# Kube_Base_ESP32_HiLetGo.net
KiCad netlist of a schematic drawn in EAGLE
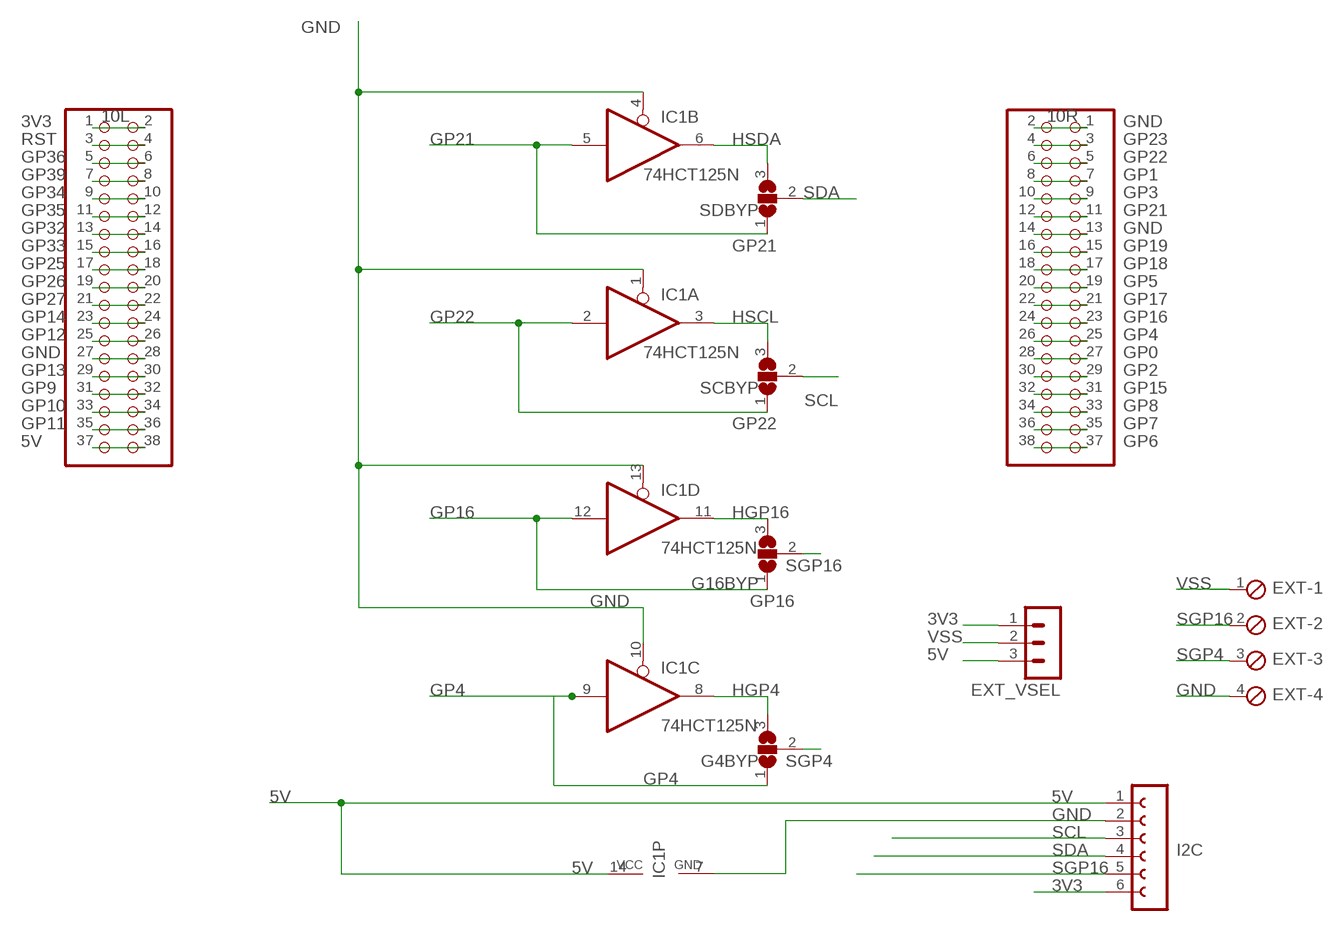
[diagram p0: schematic, sheet 1]

(export (version "E")
  (design (tool "Eeschema 10.0.6"))
  (components
    (comp (ref "10L")
      (value "15")
      (footprint "eagle-import:2X19")
      (libsource (lib "eagle-import") (part "PINHD-2X19"))
    )
    (comp (ref "10R")
      (value "15")
      (footprint "eagle-import:2X19")
      (libsource (lib "eagle-import") (part "PINHD-2X19"))
    )
    (comp (ref "EXT")
      (value "MPT4")
      (footprint "eagle-import:4POL254")
      (libsource (lib "eagle-import") (part "MPT4"))
    )
    (comp (ref "EXT_VSEL")
      (value "MA03-1")
      (footprint "eagle-import:MA03-1")
      (libsource (lib "eagle-import") (part "MA03-1"))
    )
    (comp (ref "G4BYP")
      (value "SJ2W")
      (footprint "eagle-import:SJ_2")
      (libsource (lib "eagle-import") (part "SJ2W"))
    )
    (comp (ref "G16BYP")
      (value "SJ2W")
      (footprint "eagle-import:SJ_2")
      (libsource (lib "eagle-import") (part "SJ2W"))
    )
    (comp (ref "I2C")
      (value "FE06-1")
      (footprint "eagle-import:FE06")
      (libsource (lib "eagle-import") (part "FE06-1"))
    )
    (comp (ref "IC1")
      (value "74HCT125N")
      (footprint "eagle-import:DIL14")
      (libsource (lib "eagle-import") (part "74125NHCT"))
    )
    (comp (ref "SCBYP")
      (value "SJ2W")
      (footprint "eagle-import:SJ_2")
      (libsource (lib "eagle-import") (part "SJ2W"))
    )
    (comp (ref "SDBYP")
      (value "SJ2W")
      (footprint "eagle-import:SJ_2")
      (libsource (lib "eagle-import") (part "SJ2W"))
    )
  )
  (nets
    (net (code "1") (name "/3V3") (class "Default")
      (node (ref "10L") (pin "1") (pinfunction "1_1") (pintype "passive"))
      (node (ref "10L") (pin "2") (pinfunction "2_2") (pintype "passive"))
      (node (ref "EXT_VSEL") (pin "1") (pinfunction "1_1") (pintype "passive"))
      (node (ref "I2C") (pin "6") (pinfunction "6_6") (pintype "passive"))
    )
    (net (code "2") (name "/5V") (class "Default")
      (node (ref "10L") (pin "37") (pinfunction "37_37") (pintype "passive"))
      (node (ref "10L") (pin "38") (pinfunction "38_38") (pintype "passive"))
      (node (ref "EXT_VSEL") (pin "3") (pinfunction "3_3") (pintype "passive"))
      (node (ref "I2C") (pin "1") (pinfunction "1_1") (pintype "passive"))
      (node (ref "IC1") (pin "14") (pinfunction "VCC_14") (pintype "power_in"))
    )
    (net (code "3") (name "/GND") (class "Default")
      (node (ref "10L") (pin "27") (pinfunction "27_27") (pintype "passive"))
      (node (ref "10L") (pin "28") (pinfunction "28_28") (pintype "passive"))
      (node (ref "10R") (pin "1") (pinfunction "1_1") (pintype "passive"))
      (node (ref "10R") (pin "13") (pinfunction "13_13") (pintype "passive"))
      (node (ref "10R") (pin "14") (pinfunction "14_14") (pintype "passive"))
      (node (ref "10R") (pin "2") (pinfunction "2_2") (pintype "passive"))
      (node (ref "EXT") (pin "4") (pinfunction "1_4") (pintype "passive"))
      (node (ref "I2C") (pin "2") (pinfunction "2_2") (pintype "passive"))
      (node (ref "IC1") (pin "1") (pinfunction "OE_1") (pintype "input"))
      (node (ref "IC1") (pin "10") (pinfunction "OE_10") (pintype "input"))
      (node (ref "IC1") (pin "13") (pinfunction "OE_13") (pintype "input"))
      (node (ref "IC1") (pin "4") (pinfunction "OE_4") (pintype "input"))
      (node (ref "IC1") (pin "7") (pinfunction "GND_7") (pintype "power_in"))
    )
    (net (code "4") (name "/GP0") (class "Default")
      (node (ref "10R") (pin "27") (pinfunction "27_27") (pintype "passive"))
      (node (ref "10R") (pin "28") (pinfunction "28_28") (pintype "passive"))
    )
    (net (code "5") (name "/GP1") (class "Default")
      (node (ref "10R") (pin "7") (pinfunction "7_7") (pintype "passive"))
      (node (ref "10R") (pin "8") (pinfunction "8_8") (pintype "passive"))
    )
    (net (code "6") (name "/GP2") (class "Default")
      (node (ref "10R") (pin "29") (pinfunction "29_29") (pintype "passive"))
      (node (ref "10R") (pin "30") (pinfunction "30_30") (pintype "passive"))
    )
    (net (code "7") (name "/GP3") (class "Default")
      (node (ref "10R") (pin "10") (pinfunction "10_10") (pintype "passive"))
      (node (ref "10R") (pin "9") (pinfunction "9_9") (pintype "passive"))
    )
    (net (code "8") (name "/GP4") (class "Default")
      (node (ref "10R") (pin "25") (pinfunction "25_25") (pintype "passive"))
      (node (ref "10R") (pin "26") (pinfunction "26_26") (pintype "passive"))
      (node (ref "G4BYP") (pin "1") (pinfunction "1_1") (pintype "passive"))
      (node (ref "IC1") (pin "9") (pinfunction "I_9") (pintype "input"))
    )
    (net (code "9") (name "/GP5") (class "Default")
      (node (ref "10R") (pin "19") (pinfunction "19_19") (pintype "passive"))
      (node (ref "10R") (pin "20") (pinfunction "20_20") (pintype "passive"))
    )
    (net (code "10") (name "/GP6") (class "Default")
      (node (ref "10R") (pin "37") (pinfunction "37_37") (pintype "passive"))
      (node (ref "10R") (pin "38") (pinfunction "38_38") (pintype "passive"))
    )
    (net (code "11") (name "/GP7") (class "Default")
      (node (ref "10R") (pin "35") (pinfunction "35_35") (pintype "passive"))
      (node (ref "10R") (pin "36") (pinfunction "36_36") (pintype "passive"))
    )
    (net (code "12") (name "/GP8") (class "Default")
      (node (ref "10R") (pin "33") (pinfunction "33_33") (pintype "passive"))
      (node (ref "10R") (pin "34") (pinfunction "34_34") (pintype "passive"))
    )
    (net (code "13") (name "/GP9") (class "Default")
      (node (ref "10L") (pin "31") (pinfunction "31_31") (pintype "passive"))
      (node (ref "10L") (pin "32") (pinfunction "32_32") (pintype "passive"))
    )
    (net (code "14") (name "/GP10") (class "Default")
      (node (ref "10L") (pin "33") (pinfunction "33_33") (pintype "passive"))
      (node (ref "10L") (pin "34") (pinfunction "34_34") (pintype "passive"))
    )
    (net (code "15") (name "/GP11") (class "Default")
      (node (ref "10L") (pin "35") (pinfunction "35_35") (pintype "passive"))
      (node (ref "10L") (pin "36") (pinfunction "36_36") (pintype "passive"))
    )
    (net (code "16") (name "/GP12") (class "Default")
      (node (ref "10L") (pin "25") (pinfunction "25_25") (pintype "passive"))
      (node (ref "10L") (pin "26") (pinfunction "26_26") (pintype "passive"))
    )
    (net (code "17") (name "/GP13") (class "Default")
      (node (ref "10L") (pin "29") (pinfunction "29_29") (pintype "passive"))
      (node (ref "10L") (pin "30") (pinfunction "30_30") (pintype "passive"))
    )
    (net (code "18") (name "/GP14") (class "Default")
      (node (ref "10L") (pin "23") (pinfunction "23_23") (pintype "passive"))
      (node (ref "10L") (pin "24") (pinfunction "24_24") (pintype "passive"))
    )
    (net (code "19") (name "/GP15") (class "Default")
      (node (ref "10R") (pin "31") (pinfunction "31_31") (pintype "passive"))
      (node (ref "10R") (pin "32") (pinfunction "32_32") (pintype "passive"))
    )
    (net (code "20") (name "/GP16") (class "Default")
      (node (ref "10R") (pin "23") (pinfunction "23_23") (pintype "passive"))
      (node (ref "10R") (pin "24") (pinfunction "24_24") (pintype "passive"))
      (node (ref "G16BYP") (pin "1") (pinfunction "1_1") (pintype "passive"))
      (node (ref "IC1") (pin "12") (pinfunction "I_12") (pintype "input"))
    )
    (net (code "21") (name "/GP17") (class "Default")
      (node (ref "10R") (pin "21") (pinfunction "21_21") (pintype "passive"))
      (node (ref "10R") (pin "22") (pinfunction "22_22") (pintype "passive"))
    )
    (net (code "22") (name "/GP18") (class "Default")
      (node (ref "10R") (pin "17") (pinfunction "17_17") (pintype "passive"))
      (node (ref "10R") (pin "18") (pinfunction "18_18") (pintype "passive"))
    )
    (net (code "23") (name "/GP19") (class "Default")
      (node (ref "10R") (pin "15") (pinfunction "15_15") (pintype "passive"))
      (node (ref "10R") (pin "16") (pinfunction "16_16") (pintype "passive"))
    )
    (net (code "24") (name "/GP21") (class "Default")
      (node (ref "10R") (pin "11") (pinfunction "11_11") (pintype "passive"))
      (node (ref "10R") (pin "12") (pinfunction "12_12") (pintype "passive"))
      (node (ref "IC1") (pin "5") (pinfunction "I_5") (pintype "input"))
      (node (ref "SDBYP") (pin "1") (pinfunction "1_1") (pintype "passive"))
    )
    (net (code "25") (name "/GP22") (class "Default")
      (node (ref "10R") (pin "5") (pinfunction "5_5") (pintype "passive"))
      (node (ref "10R") (pin "6") (pinfunction "6_6") (pintype "passive"))
      (node (ref "IC1") (pin "2") (pinfunction "I_2") (pintype "input"))
      (node (ref "SCBYP") (pin "1") (pinfunction "1_1") (pintype "passive"))
    )
    (net (code "26") (name "/GP23") (class "Default")
      (node (ref "10R") (pin "3") (pinfunction "3_3") (pintype "passive"))
      (node (ref "10R") (pin "4") (pinfunction "4_4") (pintype "passive"))
    )
    (net (code "27") (name "/GP25") (class "Default")
      (node (ref "10L") (pin "17") (pinfunction "17_17") (pintype "passive"))
      (node (ref "10L") (pin "18") (pinfunction "18_18") (pintype "passive"))
    )
    (net (code "28") (name "/GP26") (class "Default")
      (node (ref "10L") (pin "19") (pinfunction "19_19") (pintype "passive"))
      (node (ref "10L") (pin "20") (pinfunction "20_20") (pintype "passive"))
    )
    (net (code "29") (name "/GP27") (class "Default")
      (node (ref "10L") (pin "21") (pinfunction "21_21") (pintype "passive"))
      (node (ref "10L") (pin "22") (pinfunction "22_22") (pintype "passive"))
    )
    (net (code "30") (name "/GP32") (class "Default")
      (node (ref "10L") (pin "13") (pinfunction "13_13") (pintype "passive"))
      (node (ref "10L") (pin "14") (pinfunction "14_14") (pintype "passive"))
    )
    (net (code "31") (name "/GP33") (class "Default")
      (node (ref "10L") (pin "15") (pinfunction "15_15") (pintype "passive"))
      (node (ref "10L") (pin "16") (pinfunction "16_16") (pintype "passive"))
    )
    (net (code "32") (name "/GP34") (class "Default")
      (node (ref "10L") (pin "10") (pinfunction "10_10") (pintype "passive"))
      (node (ref "10L") (pin "9") (pinfunction "9_9") (pintype "passive"))
    )
    (net (code "33") (name "/GP35") (class "Default")
      (node (ref "10L") (pin "11") (pinfunction "11_11") (pintype "passive"))
      (node (ref "10L") (pin "12") (pinfunction "12_12") (pintype "passive"))
    )
    (net (code "34") (name "/GP36") (class "Default")
      (node (ref "10L") (pin "5") (pinfunction "5_5") (pintype "passive"))
      (node (ref "10L") (pin "6") (pinfunction "6_6") (pintype "passive"))
    )
    (net (code "35") (name "/GP39") (class "Default")
      (node (ref "10L") (pin "7") (pinfunction "7_7") (pintype "passive"))
      (node (ref "10L") (pin "8") (pinfunction "8_8") (pintype "passive"))
    )
    (net (code "36") (name "/HGP4") (class "Default")
      (node (ref "G4BYP") (pin "3") (pinfunction "3_3") (pintype "passive"))
      (node (ref "IC1") (pin "8") (pinfunction "O_8") (pintype "tri_state"))
    )
    (net (code "37") (name "/HGP16") (class "Default")
      (node (ref "G16BYP") (pin "3") (pinfunction "3_3") (pintype "passive"))
      (node (ref "IC1") (pin "11") (pinfunction "O_11") (pintype "tri_state"))
    )
    (net (code "38") (name "/HSCL") (class "Default")
      (node (ref "IC1") (pin "3") (pinfunction "O_3") (pintype "tri_state"))
      (node (ref "SCBYP") (pin "3") (pinfunction "3_3") (pintype "passive"))
    )
    (net (code "39") (name "/HSDA") (class "Default")
      (node (ref "IC1") (pin "6") (pinfunction "O_6") (pintype "tri_state"))
      (node (ref "SDBYP") (pin "3") (pinfunction "3_3") (pintype "passive"))
    )
    (net (code "40") (name "/RST") (class "Default")
      (node (ref "10L") (pin "3") (pinfunction "3_3") (pintype "passive"))
      (node (ref "10L") (pin "4") (pinfunction "4_4") (pintype "passive"))
    )
    (net (code "41") (name "/SCL") (class "Default")
      (node (ref "I2C") (pin "3") (pinfunction "3_3") (pintype "passive"))
      (node (ref "SCBYP") (pin "2") (pinfunction "2_2") (pintype "passive"))
    )
    (net (code "42") (name "/SDA") (class "Default")
      (node (ref "I2C") (pin "4") (pinfunction "4_4") (pintype "passive"))
      (node (ref "SDBYP") (pin "2") (pinfunction "2_2") (pintype "passive"))
    )
    (net (code "43") (name "/SGP4") (class "Default")
      (node (ref "EXT") (pin "3") (pinfunction "1_3") (pintype "passive"))
      (node (ref "G4BYP") (pin "2") (pinfunction "2_2") (pintype "passive"))
    )
    (net (code "44") (name "/SGP16") (class "Default")
      (node (ref "EXT") (pin "2") (pinfunction "1_2") (pintype "passive"))
      (node (ref "G16BYP") (pin "2") (pinfunction "2_2") (pintype "passive"))
      (node (ref "I2C") (pin "5") (pinfunction "5_5") (pintype "passive"))
    )
    (net (code "45") (name "/VSS") (class "Default")
      (node (ref "EXT") (pin "1") (pinfunction "1_1") (pintype "passive"))
      (node (ref "EXT_VSEL") (pin "2") (pinfunction "2_2") (pintype "passive"))
    )
  )
)
